# shield.net
KiCad netlist of a schematic drawn in EAGLE
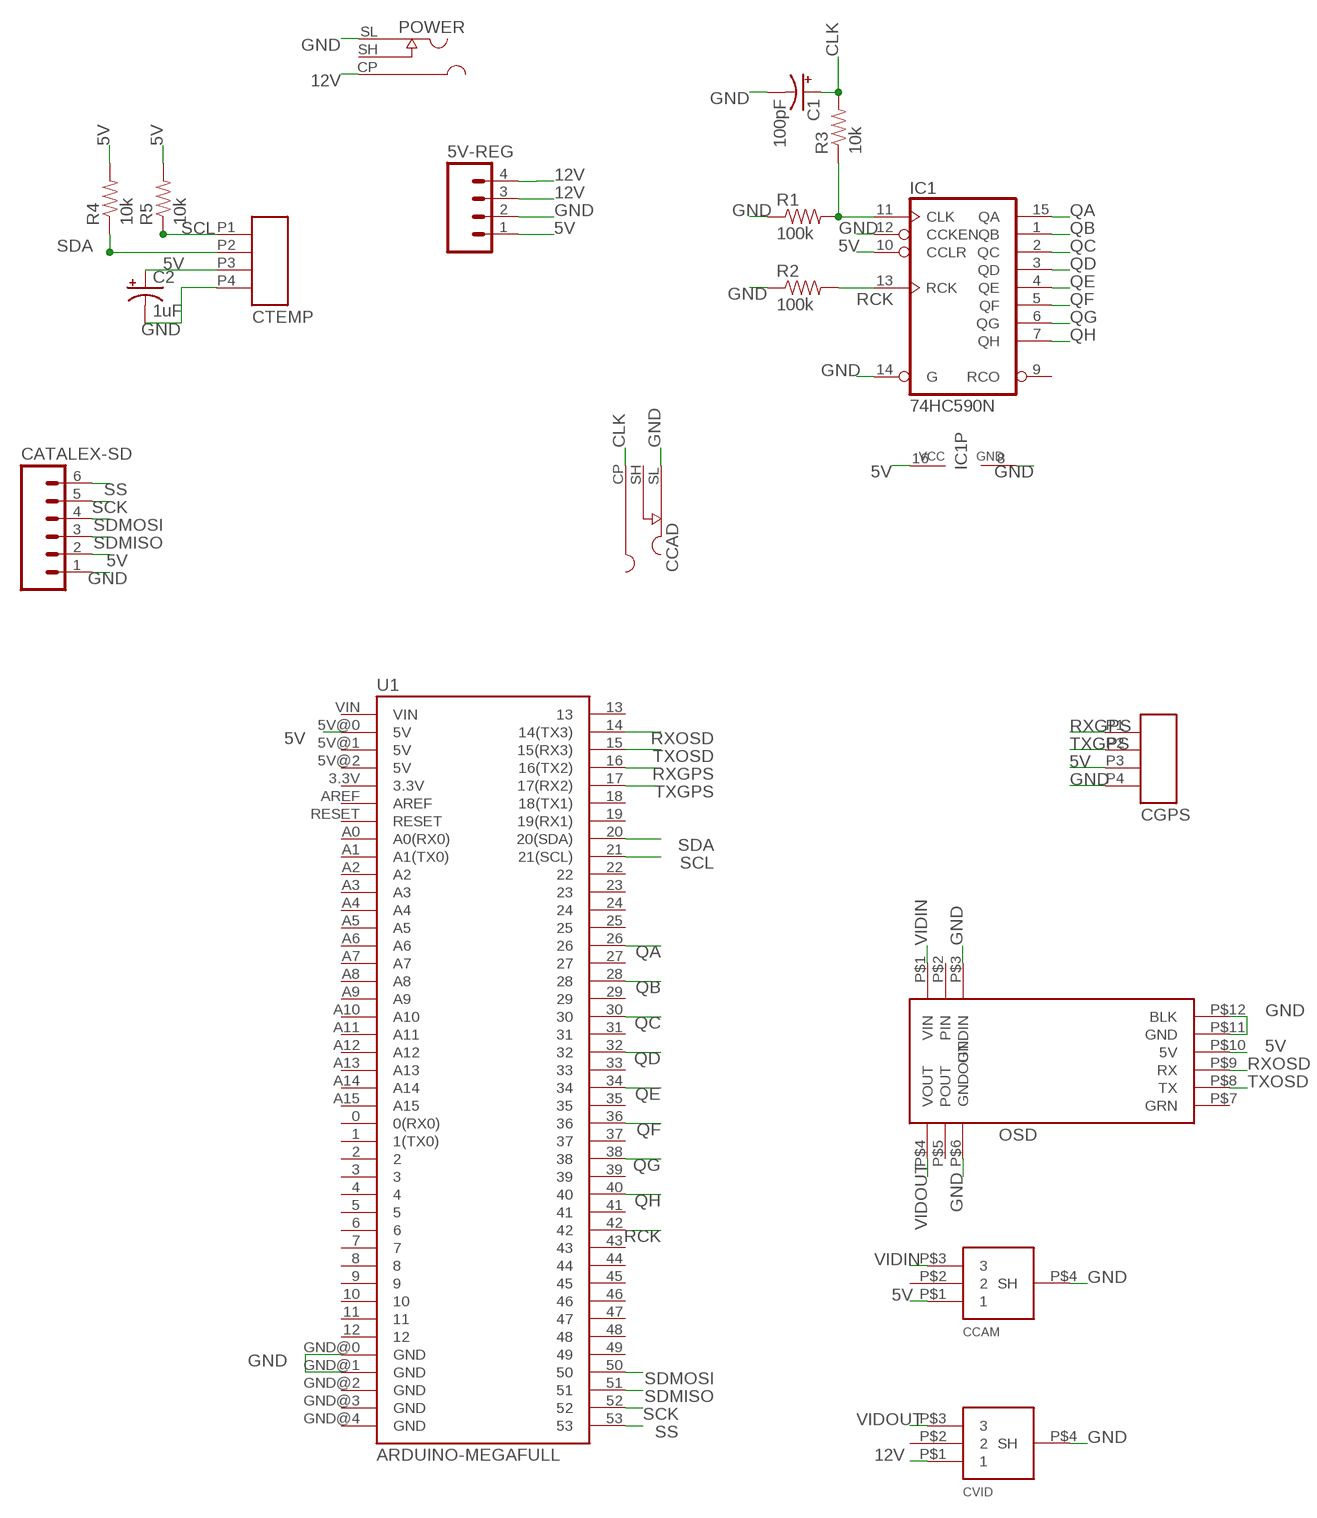
[diagram p0: schematic, sheet 1]

(export (version "E")
  (design (tool "Eeschema 10.0.6"))
  (components
    (comp (ref "5V-REG")
      (value "M041.27MM")
      (footprint "eagle-import:1X04-1.27MM")
      (libsource (lib "eagle-import") (part "M041.27MM"))
    )
    (comp (ref "C1")
      (value "100pF")
      (footprint "eagle-import:CPOL-RADIAL-10UF-25V-KIT")
      (libsource (lib "eagle-import") (part "10UF-25V-20%(PTH)KIT"))
    )
    (comp (ref "C2")
      (value "1uF")
      (footprint "eagle-import:CPOL-RADIAL-10UF-25V")
      (libsource (lib "eagle-import") (part "10UF-25V-20%(PTH)"))
    )
    (comp (ref "CATALEX-SD")
      (value "M06SILK_FEMALE_PTH")
      (footprint "eagle-import:1X06")
      (libsource (lib "eagle-import") (part "M06SILK_FEMALE_PTH"))
    )
    (comp (ref "CCAD")
      (value "L722RAS")
      (footprint "eagle-import:L722RAS")
      (libsource (lib "eagle-import") (part "L722RAS"))
    )
    (comp (ref "CCAM")
      (value "TRA3M")
      (footprint "eagle-import:TRA3M")
      (libsource (lib "eagle-import") (part "TRA3M"))
    )
    (comp (ref "CGPS")
      (value "TRAPC4MSX")
      (footprint "eagle-import:TRAPC4MSX")
      (libsource (lib "eagle-import") (part "TRAPC4MSX"))
    )
    (comp (ref "CTEMP")
      (value "TRAPC4MSX")
      (footprint "eagle-import:TRAPC4MSX")
      (libsource (lib "eagle-import") (part "TRAPC4MSX"))
    )
    (comp (ref "CVID")
      (value "TRA3M")
      (footprint "eagle-import:TRA3M")
      (libsource (lib "eagle-import") (part "TRA3M"))
    )
    (comp (ref "IC1")
      (value "74HC590N")
      (footprint "eagle-import:DIL16")
      (libsource (lib "eagle-import") (part "74590NHC"))
    )
    (comp (ref "OSD")
      (value "MINIM-OSD")
      (footprint "eagle-import:MINIM-OSD")
      (libsource (lib "eagle-import") (part "MINIM-OSD"))
    )
    (comp (ref "POWER")
      (value "L722RAS")
      (footprint "eagle-import:L722RAS")
      (libsource (lib "eagle-import") (part "L722RAS"))
    )
    (comp (ref "R1")
      (value "100k")
      (footprint "eagle-import:AXIAL-0.3EZ")
      (libsource (lib "eagle-import") (part "100KOHM-1/4W-5%(PTH)HORIZ-KIT"))
    )
    (comp (ref "R2")
      (value "100k")
      (footprint "eagle-import:AXIAL-0.3EZ")
      (libsource (lib "eagle-import") (part "100KOHM-1/4W-5%(PTH)HORIZ-KIT"))
    )
    (comp (ref "R3")
      (value "10k")
      (footprint "eagle-import:AXIAL-0.3EZ")
      (libsource (lib "eagle-import") (part "10KOHM-1/4W5%(PTH)HORIZ-KIT"))
    )
    (comp (ref "R4")
      (value "10k")
      (footprint "eagle-import:AXIAL-0.3EZ")
      (libsource (lib "eagle-import") (part "10KOHM-1/4W5%(PTH)HORIZ-KIT"))
    )
    (comp (ref "R5")
      (value "10k")
      (footprint "eagle-import:AXIAL-0.3EZ")
      (libsource (lib "eagle-import") (part "10KOHM-1/4W5%(PTH)HORIZ-KIT"))
    )
    (comp (ref "U1")
      (value "ARDUINO-MEGAFULL")
      (footprint "eagle-import:ARDUINO_MEGA")
      (libsource (lib "eagle-import") (part "ARDUINO-MEGAFULL"))
    )
  )
  (nets
    (net (code "1") (name "/5V") (class "Default")
      (node (ref "5V-REG") (pin "1") (pinfunction "1_1") (pintype "passive"))
      (node (ref "C2") (pin "1") (pinfunction "+_1") (pintype "passive"))
      (node (ref "CATALEX-SD") (pin "2") (pinfunction "2_2") (pintype "passive"))
      (node (ref "CCAM") (pin "P$1") (pinfunction "1_P$1") (pintype "bidirectional"))
      (node (ref "CGPS") (pin "P3") (pinfunction "P$3_P3") (pintype "bidirectional"))
      (node (ref "CTEMP") (pin "P3") (pinfunction "P$3_P3") (pintype "bidirectional"))
      (node (ref "IC1") (pin "10") (pinfunction "CCLR_10") (pintype "input"))
      (node (ref "IC1") (pin "16") (pinfunction "VCC_16") (pintype "power_in"))
      (node (ref "OSD") (pin "P$10") (pinfunction "5V_P$10") (pintype "bidirectional"))
      (node (ref "R4") (pin "P$2") (pinfunction "2_P$2") (pintype "passive"))
      (node (ref "R5") (pin "P$2") (pinfunction "2_P$2") (pintype "passive"))
      (node (ref "U1") (pin "5V@0") (pinfunction "5V_5V@0") (pintype "bidirectional"))
    )
    (net (code "2") (name "/12V") (class "Default")
      (node (ref "5V-REG") (pin "3") (pinfunction "3_3") (pintype "passive"))
      (node (ref "5V-REG") (pin "4") (pinfunction "4_4") (pintype "passive"))
      (node (ref "CVID") (pin "P$1") (pinfunction "1_P$1") (pintype "bidirectional"))
      (node (ref "POWER") (pin "CP") (pinfunction "CENTRE_CP") (pintype "bidirectional"))
    )
    (net (code "3") (name "/CLK") (class "Default")
      (node (ref "C1") (pin "1") (pinfunction "+_1") (pintype "passive"))
      (node (ref "CCAD") (pin "CP") (pinfunction "CENTRE_CP") (pintype "bidirectional"))
      (node (ref "R3") (pin "P$2") (pinfunction "2_P$2") (pintype "passive"))
    )
    (net (code "4") (name "/GND") (class "Default")
      (node (ref "5V-REG") (pin "2") (pinfunction "2_2") (pintype "passive"))
      (node (ref "C1") (pin "2") (pinfunction "-_2") (pintype "passive"))
      (node (ref "C2") (pin "2") (pinfunction "-_2") (pintype "passive"))
      (node (ref "CATALEX-SD") (pin "1") (pinfunction "1_1") (pintype "passive"))
      (node (ref "CCAD") (pin "SL") (pinfunction "SLEEVE_SL") (pintype "bidirectional"))
      (node (ref "CCAM") (pin "P$4") (pinfunction "SH_P$4") (pintype "bidirectional"))
      (node (ref "CGPS") (pin "P4") (pinfunction "P$4_P4") (pintype "bidirectional"))
      (node (ref "CTEMP") (pin "P4") (pinfunction "P$4_P4") (pintype "bidirectional"))
      (node (ref "CVID") (pin "P$4") (pinfunction "SH_P$4") (pintype "bidirectional"))
      (node (ref "IC1") (pin "12") (pinfunction "CCKEN_12") (pintype "input"))
      (node (ref "IC1") (pin "14") (pinfunction "G_14") (pintype "input"))
      (node (ref "IC1") (pin "8") (pinfunction "GND_8") (pintype "power_in"))
      (node (ref "OSD") (pin "P$11") (pinfunction "GND_P$11") (pintype "bidirectional"))
      (node (ref "OSD") (pin "P$12") (pinfunction "BLK_P$12") (pintype "bidirectional"))
      (node (ref "OSD") (pin "P$3") (pinfunction "GNDIN_P$3") (pintype "bidirectional"))
      (node (ref "OSD") (pin "P$6") (pinfunction "GNDOUT_P$6") (pintype "bidirectional"))
      (node (ref "POWER") (pin "SL") (pinfunction "SLEEVE_SL") (pintype "bidirectional"))
      (node (ref "R1") (pin "P$1") (pinfunction "1_P$1") (pintype "passive"))
      (node (ref "R2") (pin "P$1") (pinfunction "1_P$1") (pintype "passive"))
      (node (ref "U1") (pin "GND@0") (pinfunction "GND_GND@0") (pintype "bidirectional"))
      (node (ref "U1") (pin "GND@1") (pinfunction "GND_GND@1") (pintype "bidirectional"))
    )
    (net (code "5") (name "/QA") (class "Default")
      (node (ref "IC1") (pin "15") (pinfunction "QA_15") (pintype "tri_state"))
      (node (ref "U1") (pin "26") (pinfunction "26_26") (pintype "bidirectional"))
    )
    (net (code "6") (name "/QB") (class "Default")
      (node (ref "IC1") (pin "1") (pinfunction "QB_1") (pintype "tri_state"))
      (node (ref "U1") (pin "28") (pinfunction "28_28") (pintype "bidirectional"))
    )
    (net (code "7") (name "/QC") (class "Default")
      (node (ref "IC1") (pin "2") (pinfunction "QC_2") (pintype "tri_state"))
      (node (ref "U1") (pin "30") (pinfunction "30_30") (pintype "bidirectional"))
    )
    (net (code "8") (name "/QD") (class "Default")
      (node (ref "IC1") (pin "3") (pinfunction "QD_3") (pintype "tri_state"))
      (node (ref "U1") (pin "32") (pinfunction "32_32") (pintype "bidirectional"))
    )
    (net (code "9") (name "/QE") (class "Default")
      (node (ref "IC1") (pin "4") (pinfunction "QE_4") (pintype "tri_state"))
      (node (ref "U1") (pin "34") (pinfunction "34_34") (pintype "bidirectional"))
    )
    (net (code "10") (name "/QF") (class "Default")
      (node (ref "IC1") (pin "5") (pinfunction "QF_5") (pintype "tri_state"))
      (node (ref "U1") (pin "36") (pinfunction "36_36") (pintype "bidirectional"))
    )
    (net (code "11") (name "/QG") (class "Default")
      (node (ref "IC1") (pin "6") (pinfunction "QG_6") (pintype "tri_state"))
      (node (ref "U1") (pin "38") (pinfunction "38_38") (pintype "bidirectional"))
    )
    (net (code "12") (name "/QH") (class "Default")
      (node (ref "IC1") (pin "7") (pinfunction "QH_7") (pintype "tri_state"))
      (node (ref "U1") (pin "40") (pinfunction "40_40") (pintype "bidirectional"))
    )
    (net (code "13") (name "/RCK") (class "Default")
      (node (ref "IC1") (pin "13") (pinfunction "RCK_13") (pintype "input"))
      (node (ref "R2") (pin "P$2") (pinfunction "2_P$2") (pintype "passive"))
      (node (ref "U1") (pin "42") (pinfunction "42_42") (pintype "bidirectional"))
    )
    (net (code "14") (name "/RXGPS") (class "Default")
      (node (ref "CGPS") (pin "P1") (pinfunction "P$1_P1") (pintype "bidirectional"))
      (node (ref "U1") (pin "16") (pinfunction "16(TX2)_16") (pintype "bidirectional"))
    )
    (net (code "15") (name "/RXOSD") (class "Default")
      (node (ref "OSD") (pin "P$9") (pinfunction "RX_P$9") (pintype "bidirectional"))
      (node (ref "U1") (pin "14") (pinfunction "14(TX3)_14") (pintype "bidirectional"))
    )
    (net (code "16") (name "/SCK") (class "Default")
      (node (ref "CATALEX-SD") (pin "5") (pinfunction "5_5") (pintype "passive"))
      (node (ref "U1") (pin "52") (pinfunction "52_52") (pintype "bidirectional"))
    )
    (net (code "17") (name "/SCL") (class "Default")
      (node (ref "CTEMP") (pin "P1") (pinfunction "P$1_P1") (pintype "bidirectional"))
      (node (ref "R5") (pin "P$1") (pinfunction "1_P$1") (pintype "passive"))
      (node (ref "U1") (pin "21") (pinfunction "21(SCL)_21") (pintype "bidirectional"))
    )
    (net (code "18") (name "/SDA") (class "Default")
      (node (ref "CTEMP") (pin "P2") (pinfunction "P$2_P2") (pintype "bidirectional"))
      (node (ref "R4") (pin "P$1") (pinfunction "1_P$1") (pintype "passive"))
      (node (ref "U1") (pin "20") (pinfunction "20(SDA)_20") (pintype "bidirectional"))
    )
    (net (code "19") (name "/SDMISO") (class "Default")
      (node (ref "CATALEX-SD") (pin "3") (pinfunction "3_3") (pintype "passive"))
      (node (ref "U1") (pin "51") (pinfunction "51_51") (pintype "bidirectional"))
    )
    (net (code "20") (name "/SDMOSI") (class "Default")
      (node (ref "CATALEX-SD") (pin "4") (pinfunction "4_4") (pintype "passive"))
      (node (ref "U1") (pin "50") (pinfunction "50_50") (pintype "bidirectional"))
    )
    (net (code "21") (name "/SS") (class "Default")
      (node (ref "CATALEX-SD") (pin "6") (pinfunction "6_6") (pintype "passive"))
      (node (ref "U1") (pin "53") (pinfunction "53_53") (pintype "bidirectional"))
    )
    (net (code "22") (name "/TXGPS") (class "Default")
      (node (ref "CGPS") (pin "P2") (pinfunction "P$2_P2") (pintype "bidirectional"))
      (node (ref "U1") (pin "17") (pinfunction "17(RX2)_17") (pintype "bidirectional"))
    )
    (net (code "23") (name "/TXOSD") (class "Default")
      (node (ref "OSD") (pin "P$8") (pinfunction "TX_P$8") (pintype "bidirectional"))
      (node (ref "U1") (pin "15") (pinfunction "15(RX3)_15") (pintype "bidirectional"))
    )
    (net (code "24") (name "/VIDIN") (class "Default")
      (node (ref "CCAM") (pin "P$3") (pinfunction "3_P$3") (pintype "bidirectional"))
      (node (ref "OSD") (pin "P$1") (pinfunction "VIN_P$1") (pintype "bidirectional"))
    )
    (net (code "25") (name "/VIDOUT") (class "Default")
      (node (ref "CVID") (pin "P$3") (pinfunction "3_P$3") (pintype "bidirectional"))
      (node (ref "OSD") (pin "P$4") (pinfunction "VOUT_P$4") (pintype "bidirectional"))
    )
    (net (code "26") (name "Net-(IC1A-CLK)") (class "Default")
      (node (ref "IC1") (pin "11") (pinfunction "CLK_11") (pintype "input"))
      (node (ref "R1") (pin "P$2") (pinfunction "2_P$2") (pintype "passive"))
      (node (ref "R3") (pin "P$1") (pinfunction "1_P$1") (pintype "passive"))
    )
    (net (code "27") (name "unconnected-(CCAD-SHUNT-PadSH)") (class "Default")
      (node (ref "CCAD") (pin "SH") (pinfunction "SHUNT_SH") (pintype "bidirectional"))
    )
    (net (code "28") (name "unconnected-(CCAM-2-PadP$2)") (class "Default")
      (node (ref "CCAM") (pin "P$2") (pinfunction "2_P$2") (pintype "bidirectional"))
    )
    (net (code "29") (name "unconnected-(CVID-2-PadP$2)") (class "Default")
      (node (ref "CVID") (pin "P$2") (pinfunction "2_P$2") (pintype "bidirectional"))
    )
    (net (code "30") (name "unconnected-(IC1A-RCO-Pad9)") (class "Default")
      (node (ref "IC1") (pin "9") (pinfunction "RCO_9") (pintype "output"))
    )
    (net (code "31") (name "unconnected-(OSD-GRN-PadP$7)") (class "Default")
      (node (ref "OSD") (pin "P$7") (pinfunction "GRN_P$7") (pintype "bidirectional"))
    )
    (net (code "32") (name "unconnected-(OSD-PIN-PadP$2)") (class "Default")
      (node (ref "OSD") (pin "P$2") (pinfunction "PIN_P$2") (pintype "bidirectional"))
    )
    (net (code "33") (name "unconnected-(OSD-POUT-PadP$5)") (class "Default")
      (node (ref "OSD") (pin "P$5") (pinfunction "POUT_P$5") (pintype "bidirectional"))
    )
    (net (code "34") (name "unconnected-(POWER-SHUNT-PadSH)") (class "Default")
      (node (ref "POWER") (pin "SH") (pinfunction "SHUNT_SH") (pintype "bidirectional"))
    )
    (net (code "35") (name "unconnected-(U1-0(RX0)-Pad0)") (class "Default")
      (node (ref "U1") (pin "0") (pinfunction "0(RX0)_0") (pintype "bidirectional"))
    )
    (net (code "36") (name "unconnected-(U1-1(TX0)-Pad1)") (class "Default")
      (node (ref "U1") (pin "1") (pinfunction "1(TX0)_1") (pintype "bidirectional"))
    )
    (net (code "37") (name "unconnected-(U1-5V-Pad5V@1)") (class "Default")
      (node (ref "U1") (pin "5V@1") (pinfunction "5V_5V@1") (pintype "bidirectional"))
    )
    (net (code "38") (name "unconnected-(U1-5V-Pad5V@2)") (class "Default")
      (node (ref "U1") (pin "5V@2") (pinfunction "5V_5V@2") (pintype "bidirectional"))
    )
    (net (code "39") (name "unconnected-(U1-18(TX1)-Pad18)") (class "Default")
      (node (ref "U1") (pin "18") (pinfunction "18(TX1)_18") (pintype "bidirectional"))
    )
    (net (code "40") (name "unconnected-(U1-19(RX1)-Pad19)") (class "Default")
      (node (ref "U1") (pin "19") (pinfunction "19(RX1)_19") (pintype "bidirectional"))
    )
    (net (code "41") (name "unconnected-(U1-A0(RX0)-PadA0)") (class "Default")
      (node (ref "U1") (pin "A0") (pinfunction "A0(RX0)_A0") (pintype "bidirectional"))
    )
    (net (code "42") (name "unconnected-(U1-A1(TX0)-PadA1)") (class "Default")
      (node (ref "U1") (pin "A1") (pinfunction "A1(TX0)_A1") (pintype "bidirectional"))
    )
    (net (code "43") (name "unconnected-(U1-GND-PadGND@2)") (class "Default")
      (node (ref "U1") (pin "GND@2") (pinfunction "GND_GND@2") (pintype "bidirectional"))
    )
    (net (code "44") (name "unconnected-(U1-GND-PadGND@3)") (class "Default")
      (node (ref "U1") (pin "GND@3") (pinfunction "GND_GND@3") (pintype "bidirectional"))
    )
    (net (code "45") (name "unconnected-(U1-GND-PadGND@4)") (class "Default")
      (node (ref "U1") (pin "GND@4") (pinfunction "GND_GND@4") (pintype "bidirectional"))
    )
    (net (code "46") (name "unconnected-(U1-Pad2)") (class "Default")
      (node (ref "U1") (pin "2") (pinfunction "2_2") (pintype "bidirectional"))
    )
    (net (code "47") (name "unconnected-(U1-Pad3)") (class "Default")
      (node (ref "U1") (pin "3") (pinfunction "3_3") (pintype "bidirectional"))
    )
    (net (code "48") (name "unconnected-(U1-Pad3.3V)") (class "Default")
      (node (ref "U1") (pin "3.3V") (pinfunction "3.3V_3.3V") (pintype "bidirectional"))
    )
    (net (code "49") (name "unconnected-(U1-Pad4)") (class "Default")
      (node (ref "U1") (pin "4") (pinfunction "4_4") (pintype "bidirectional"))
    )
    (net (code "50") (name "unconnected-(U1-Pad5)") (class "Default")
      (node (ref "U1") (pin "5") (pinfunction "5_5") (pintype "bidirectional"))
    )
    (net (code "51") (name "unconnected-(U1-Pad6)") (class "Default")
      (node (ref "U1") (pin "6") (pinfunction "6_6") (pintype "bidirectional"))
    )
    (net (code "52") (name "unconnected-(U1-Pad7)") (class "Default")
      (node (ref "U1") (pin "7") (pinfunction "7_7") (pintype "bidirectional"))
    )
    (net (code "53") (name "unconnected-(U1-Pad8)") (class "Default")
      (node (ref "U1") (pin "8") (pinfunction "8_8") (pintype "bidirectional"))
    )
    (net (code "54") (name "unconnected-(U1-Pad9)") (class "Default")
      (node (ref "U1") (pin "9") (pinfunction "9_9") (pintype "bidirectional"))
    )
    (net (code "55") (name "unconnected-(U1-Pad10)") (class "Default")
      (node (ref "U1") (pin "10") (pinfunction "10_10") (pintype "bidirectional"))
    )
    (net (code "56") (name "unconnected-(U1-Pad11)") (class "Default")
      (node (ref "U1") (pin "11") (pinfunction "11_11") (pintype "bidirectional"))
    )
    (net (code "57") (name "unconnected-(U1-Pad12)") (class "Default")
      (node (ref "U1") (pin "12") (pinfunction "12_12") (pintype "bidirectional"))
    )
    (net (code "58") (name "unconnected-(U1-Pad13)") (class "Default")
      (node (ref "U1") (pin "13") (pinfunction "13_13") (pintype "bidirectional"))
    )
    (net (code "59") (name "unconnected-(U1-Pad22)") (class "Default")
      (node (ref "U1") (pin "22") (pinfunction "22_22") (pintype "bidirectional"))
    )
    (net (code "60") (name "unconnected-(U1-Pad23)") (class "Default")
      (node (ref "U1") (pin "23") (pinfunction "23_23") (pintype "bidirectional"))
    )
    (net (code "61") (name "unconnected-(U1-Pad24)") (class "Default")
      (node (ref "U1") (pin "24") (pinfunction "24_24") (pintype "bidirectional"))
    )
    (net (code "62") (name "unconnected-(U1-Pad25)") (class "Default")
      (node (ref "U1") (pin "25") (pinfunction "25_25") (pintype "bidirectional"))
    )
    (net (code "63") (name "unconnected-(U1-Pad27)") (class "Default")
      (node (ref "U1") (pin "27") (pinfunction "27_27") (pintype "bidirectional"))
    )
    (net (code "64") (name "unconnected-(U1-Pad29)") (class "Default")
      (node (ref "U1") (pin "29") (pinfunction "29_29") (pintype "bidirectional"))
    )
    (net (code "65") (name "unconnected-(U1-Pad31)") (class "Default")
      (node (ref "U1") (pin "31") (pinfunction "31_31") (pintype "bidirectional"))
    )
    (net (code "66") (name "unconnected-(U1-Pad33)") (class "Default")
      (node (ref "U1") (pin "33") (pinfunction "33_33") (pintype "bidirectional"))
    )
    (net (code "67") (name "unconnected-(U1-Pad35)") (class "Default")
      (node (ref "U1") (pin "35") (pinfunction "35_35") (pintype "bidirectional"))
    )
    (net (code "68") (name "unconnected-(U1-Pad37)") (class "Default")
      (node (ref "U1") (pin "37") (pinfunction "37_37") (pintype "bidirectional"))
    )
    (net (code "69") (name "unconnected-(U1-Pad39)") (class "Default")
      (node (ref "U1") (pin "39") (pinfunction "39_39") (pintype "bidirectional"))
    )
    (net (code "70") (name "unconnected-(U1-Pad41)") (class "Default")
      (node (ref "U1") (pin "41") (pinfunction "41_41") (pintype "bidirectional"))
    )
    (net (code "71") (name "unconnected-(U1-Pad43)") (class "Default")
      (node (ref "U1") (pin "43") (pinfunction "43_43") (pintype "bidirectional"))
    )
    (net (code "72") (name "unconnected-(U1-Pad44)") (class "Default")
      (node (ref "U1") (pin "44") (pinfunction "44_44") (pintype "bidirectional"))
    )
    (net (code "73") (name "unconnected-(U1-Pad45)") (class "Default")
      (node (ref "U1") (pin "45") (pinfunction "45_45") (pintype "bidirectional"))
    )
    (net (code "74") (name "unconnected-(U1-Pad46)") (class "Default")
      (node (ref "U1") (pin "46") (pinfunction "46_46") (pintype "bidirectional"))
    )
    (net (code "75") (name "unconnected-(U1-Pad47)") (class "Default")
      (node (ref "U1") (pin "47") (pinfunction "47_47") (pintype "bidirectional"))
    )
    (net (code "76") (name "unconnected-(U1-Pad48)") (class "Default")
      (node (ref "U1") (pin "48") (pinfunction "48_48") (pintype "bidirectional"))
    )
    (net (code "77") (name "unconnected-(U1-Pad49)") (class "Default")
      (node (ref "U1") (pin "49") (pinfunction "49_49") (pintype "bidirectional"))
    )
    (net (code "78") (name "unconnected-(U1-PadA2)") (class "Default")
      (node (ref "U1") (pin "A2") (pinfunction "A2_A2") (pintype "bidirectional"))
    )
    (net (code "79") (name "unconnected-(U1-PadA3)") (class "Default")
      (node (ref "U1") (pin "A3") (pinfunction "A3_A3") (pintype "bidirectional"))
    )
    (net (code "80") (name "unconnected-(U1-PadA4)") (class "Default")
      (node (ref "U1") (pin "A4") (pinfunction "A4_A4") (pintype "bidirectional"))
    )
    (net (code "81") (name "unconnected-(U1-PadA5)") (class "Default")
      (node (ref "U1") (pin "A5") (pinfunction "A5_A5") (pintype "bidirectional"))
    )
    (net (code "82") (name "unconnected-(U1-PadA6)") (class "Default")
      (node (ref "U1") (pin "A6") (pinfunction "A6_A6") (pintype "bidirectional"))
    )
    (net (code "83") (name "unconnected-(U1-PadA7)") (class "Default")
      (node (ref "U1") (pin "A7") (pinfunction "A7_A7") (pintype "bidirectional"))
    )
    (net (code "84") (name "unconnected-(U1-PadA8)") (class "Default")
      (node (ref "U1") (pin "A8") (pinfunction "A8_A8") (pintype "bidirectional"))
    )
    (net (code "85") (name "unconnected-(U1-PadA9)") (class "Default")
      (node (ref "U1") (pin "A9") (pinfunction "A9_A9") (pintype "bidirectional"))
    )
    (net (code "86") (name "unconnected-(U1-PadA10)") (class "Default")
      (node (ref "U1") (pin "A10") (pinfunction "A10_A10") (pintype "bidirectional"))
    )
    (net (code "87") (name "unconnected-(U1-PadA11)") (class "Default")
      (node (ref "U1") (pin "A11") (pinfunction "A11_A11") (pintype "bidirectional"))
    )
    (net (code "88") (name "unconnected-(U1-PadA12)") (class "Default")
      (node (ref "U1") (pin "A12") (pinfunction "A12_A12") (pintype "bidirectional"))
    )
    (net (code "89") (name "unconnected-(U1-PadA13)") (class "Default")
      (node (ref "U1") (pin "A13") (pinfunction "A13_A13") (pintype "bidirectional"))
    )
    (net (code "90") (name "unconnected-(U1-PadA14)") (class "Default")
      (node (ref "U1") (pin "A14") (pinfunction "A14_A14") (pintype "bidirectional"))
    )
    (net (code "91") (name "unconnected-(U1-PadA15)") (class "Default")
      (node (ref "U1") (pin "A15") (pinfunction "A15_A15") (pintype "bidirectional"))
    )
    (net (code "92") (name "unconnected-(U1-PadAREF)") (class "Default")
      (node (ref "U1") (pin "AREF") (pinfunction "AREF_AREF") (pintype "bidirectional"))
    )
    (net (code "93") (name "unconnected-(U1-PadRESET)") (class "Default")
      (node (ref "U1") (pin "RESET") (pinfunction "RESET_RESET") (pintype "bidirectional"))
    )
    (net (code "94") (name "unconnected-(U1-PadVIN)") (class "Default")
      (node (ref "U1") (pin "VIN") (pinfunction "VIN_VIN") (pintype "bidirectional"))
    )
  )
)
